# fan_light_module.net
KiCad netlist of a schematic drawn in EAGLE
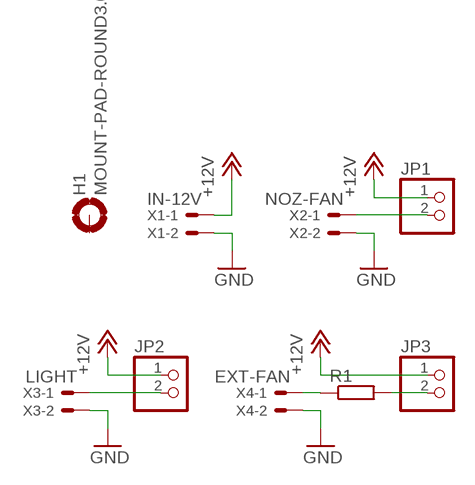
[diagram p0: schematic, sheet 1]

(export (version "E")
  (design (tool "Eeschema 10.0.6"))
  (components
    (comp (ref "H1")
      (value "MOUNT-PAD-ROUND3.0")
      (footprint "eagle-import:3,0-PAD")
      (libsource (lib "eagle-import") (part "MOUNT-PAD-ROUND3.0"))
    )
    (comp (ref "JP1")
      (value "PINHD-1X2")
      (footprint "eagle-import:1X02")
      (libsource (lib "eagle-import") (part "PINHD-1X2"))
    )
    (comp (ref "JP2")
      (value "PINHD-1X2")
      (footprint "eagle-import:1X02")
      (libsource (lib "eagle-import") (part "PINHD-1X2"))
    )
    (comp (ref "JP3")
      (value "PINHD-1X2")
      (footprint "eagle-import:1X02")
      (libsource (lib "eagle-import") (part "PINHD-1X2"))
    )
    (comp (ref "R1")
      (value "R-EU_0204/7")
      (footprint "eagle-import:0204_7")
      (libsource (lib "eagle-import") (part "R-EU_0204/7"))
    )
    (comp (ref "X1")
      (value "IN-12V")
      (footprint "eagle-import:JST-XH-02-PACKAGE-LONG-PAD")
      (libsource (lib "eagle-import") (part "JST-XH-02-PIN-LONG-PAD"))
    )
    (comp (ref "X2")
      (value "NOZ-FAN")
      (footprint "eagle-import:JST-XH-02-PACKAGE-LONG-PAD")
      (libsource (lib "eagle-import") (part "JST-XH-02-PIN-LONG-PAD"))
    )
    (comp (ref "X3")
      (value "LIGHT")
      (footprint "eagle-import:JST-XH-02-PACKAGE-LONG-PAD")
      (libsource (lib "eagle-import") (part "JST-XH-02-PIN-LONG-PAD"))
    )
    (comp (ref "X4")
      (value "EXT-FAN")
      (footprint "eagle-import:JST-XH-02-PACKAGE-LONG-PAD")
      (libsource (lib "eagle-import") (part "JST-XH-02-PIN-LONG-PAD"))
    )
  )
  (nets
    (net (code "1") (name "+12V") (class "Default")
      (node (ref "JP1") (pin "1") (pinfunction "1_1") (pintype "passive"))
      (node (ref "JP2") (pin "1") (pinfunction "1_1") (pintype "passive"))
      (node (ref "JP3") (pin "1") (pinfunction "1_1") (pintype "passive"))
      (node (ref "X1") (pin "1") (pinfunction "S_1") (pintype "passive"))
    )
    (net (code "2") (name "GND") (class "Default")
      (node (ref "X1") (pin "2") (pinfunction "S_2") (pintype "passive"))
      (node (ref "X2") (pin "2") (pinfunction "S_2") (pintype "passive"))
      (node (ref "X3") (pin "2") (pinfunction "S_2") (pintype "passive"))
      (node (ref "X4") (pin "2") (pinfunction "S_2") (pintype "passive"))
    )
    (net (code "3") (name "Net-(JP3-Pad2)") (class "Default")
      (node (ref "JP3") (pin "2") (pinfunction "2_2") (pintype "passive"))
      (node (ref "R1") (pin "2") (pinfunction "2_2") (pintype "passive"))
    )
    (net (code "4") (name "Net-(X2A-S)") (class "Default")
      (node (ref "JP1") (pin "2") (pinfunction "2_2") (pintype "passive"))
      (node (ref "X2") (pin "1") (pinfunction "S_1") (pintype "passive"))
    )
    (net (code "5") (name "Net-(X3A-S)") (class "Default")
      (node (ref "JP2") (pin "2") (pinfunction "2_2") (pintype "passive"))
      (node (ref "X3") (pin "1") (pinfunction "S_1") (pintype "passive"))
    )
    (net (code "6") (name "Net-(X4A-S)") (class "Default")
      (node (ref "R1") (pin "1") (pinfunction "1_1") (pintype "passive"))
      (node (ref "X4") (pin "1") (pinfunction "S_1") (pintype "passive"))
    )
    (net (code "7") (name "unconnected-(H1-MOUNT-PadB3,0)") (class "Default")
      (node (ref "H1") (pin "B3,0") (pinfunction "MOUNT_B3,0") (pintype "passive"))
    )
  )
)
